# giraffe_bosch.net
KiCad netlist of a schematic drawn in EAGLE
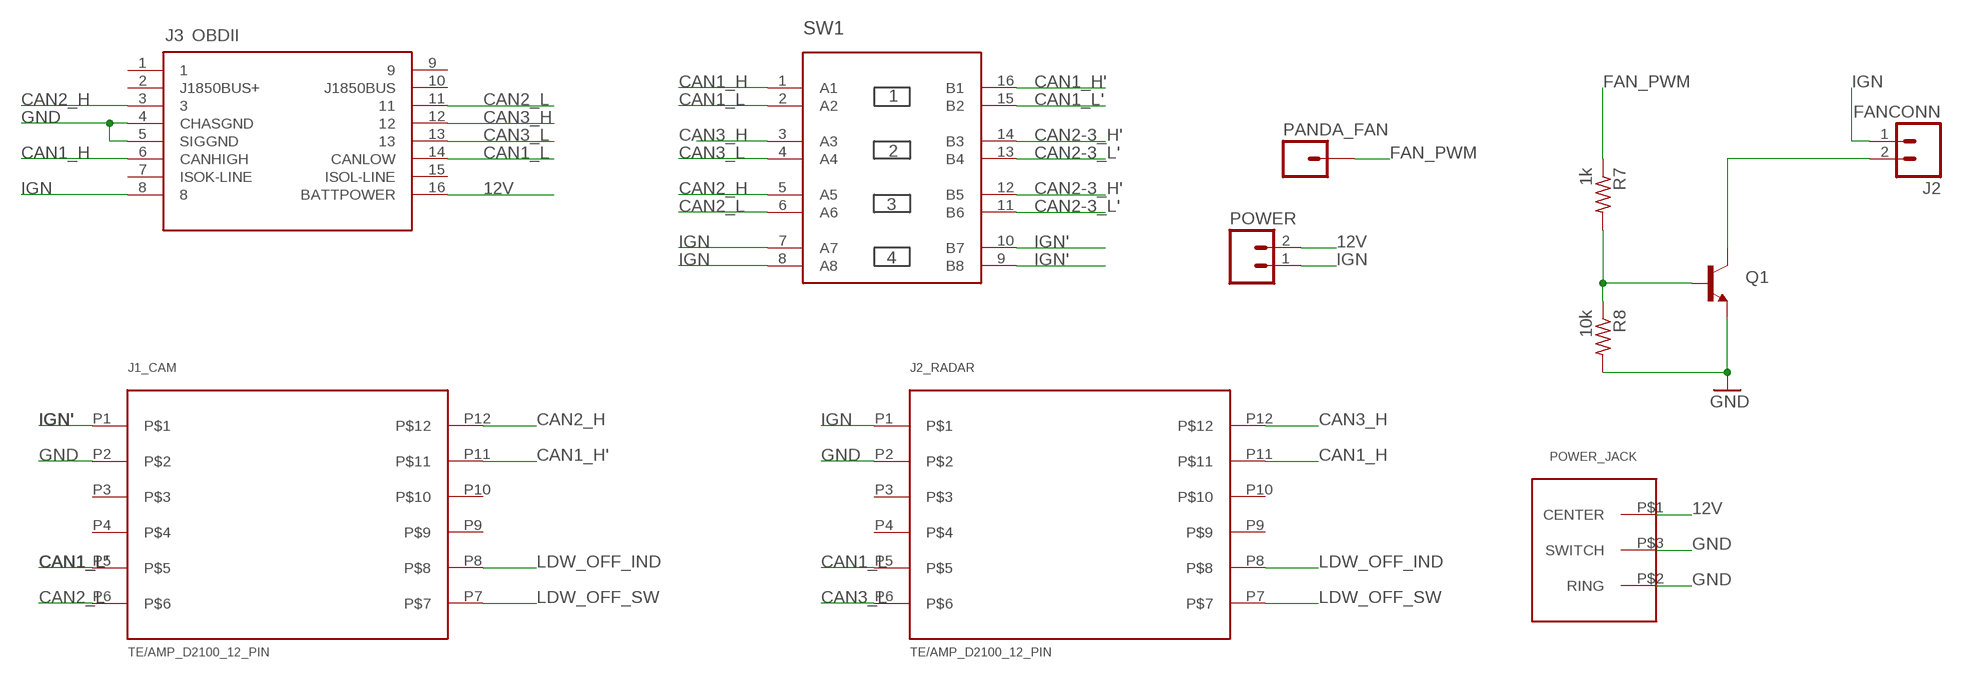
[diagram p0: schematic, sheet 1]

(export (version "E")
  (design (tool "Eeschema 10.0.6"))
  (components
    (comp (ref "J1_CAM")
      (value "TE/AMP_D2100_12_PIN")
      (footprint "eagle-import:TE_AMP_D2100_12_PIN")
      (libsource (lib "eagle-import") (part "TE/AMP_D2100_12_PIN"))
    )
    (comp (ref "J2")
      (value "FANCONN")
      (footprint "eagle-import:1.25CONN")
      (libsource (lib "eagle-import") (part "FANCONN"))
    )
    (comp (ref "J2_RADAR")
      (value "TE/AMP_D2100_12_PIN")
      (footprint "eagle-import:TE_AMP_D2100_12_PIN")
      (libsource (lib "eagle-import") (part "TE/AMP_D2100_12_PIN"))
    )
    (comp (ref "J3")
      (value "OBDIIFEMALE")
      (footprint "eagle-import:OBDII-FEMALE")
      (libsource (lib "eagle-import") (part "OBDIIFEMALE"))
    )
    (comp (ref "PANDA_FAN")
      (value "M01PTH")
      (footprint "eagle-import:1X01")
      (libsource (lib "eagle-import") (part "M01PTH"))
    )
    (comp (ref "POWER")
      (value "M02PTH")
      (footprint "eagle-import:1X02")
      (libsource (lib "eagle-import") (part "M02PTH"))
    )
    (comp (ref "POWER_JACK")
      (value "PJ-006A-SMT")
      (footprint "eagle-import:PJ-006A-SMT")
      (libsource (lib "eagle-import") (part "PJ-006A-SMT"))
    )
    (comp (ref "Q1")
      (value "MMBT2222A")
      (footprint "eagle-import:SOT23-3")
      (libsource (lib "eagle-import") (part "TRANSISTOR_NPNMMBT2222A"))
    )
    (comp (ref "R7")
      (value "1k")
      (footprint "eagle-import:R0603")
      (libsource (lib "eagle-import") (part "R-US_R0603"))
    )
    (comp (ref "R8")
      (value "10k")
      (footprint "eagle-import:R0603")
      (libsource (lib "eagle-import") (part "R-US_R0603"))
    )
    (comp (ref "SW1")
      (value "4XDPSTSMT")
      (footprint "eagle-import:4-DPST")
      (libsource (lib "eagle-import") (part "4XDPSTSMT"))
    )
  )
  (nets
    (net (code "1") (name "/12V") (class "Default")
      (node (ref "J3") (pin "16") (pinfunction "BATTPOWER_16") (pintype "bidirectional"))
      (node (ref "POWER") (pin "2") (pinfunction "2_2") (pintype "passive"))
      (node (ref "POWER_JACK") (pin "P$1") (pinfunction "CENTER_P$1") (pintype "power_in"))
    )
    (net (code "2") (name "/CAN1_H") (class "Default")
      (node (ref "J2_RADAR") (pin "P11") (pinfunction "P$11_P11") (pintype "bidirectional"))
      (node (ref "J3") (pin "6") (pinfunction "CANHIGH_6") (pintype "bidirectional"))
      (node (ref "SW1") (pin "1") (pinfunction "A1_1") (pintype "bidirectional"))
    )
    (net (code "3") (name "/CAN1_H'") (class "Default")
      (node (ref "J1_CAM") (pin "P11") (pinfunction "P$11_P11") (pintype "bidirectional"))
      (node (ref "SW1") (pin "16") (pinfunction "B1_16") (pintype "bidirectional"))
    )
    (net (code "4") (name "/CAN1_L") (class "Default")
      (node (ref "J2_RADAR") (pin "P5") (pinfunction "P$5_P5") (pintype "bidirectional"))
      (node (ref "J3") (pin "14") (pinfunction "CANLOW_14") (pintype "bidirectional"))
      (node (ref "SW1") (pin "2") (pinfunction "A2_2") (pintype "bidirectional"))
    )
    (net (code "5") (name "/CAN1_L'") (class "Default")
      (node (ref "J1_CAM") (pin "P5") (pinfunction "P$5_P5") (pintype "bidirectional"))
      (node (ref "SW1") (pin "15") (pinfunction "B2_15") (pintype "bidirectional"))
    )
    (net (code "6") (name "/CAN2-3_H'") (class "Default")
      (node (ref "SW1") (pin "12") (pinfunction "B5_12") (pintype "bidirectional"))
      (node (ref "SW1") (pin "14") (pinfunction "B3_14") (pintype "bidirectional"))
    )
    (net (code "7") (name "/CAN2-3_L'") (class "Default")
      (node (ref "SW1") (pin "11") (pinfunction "B6_11") (pintype "bidirectional"))
      (node (ref "SW1") (pin "13") (pinfunction "B4_13") (pintype "bidirectional"))
    )
    (net (code "8") (name "/CAN2_H") (class "Default")
      (node (ref "J1_CAM") (pin "P12") (pinfunction "P$12_P12") (pintype "bidirectional"))
      (node (ref "J3") (pin "3") (pinfunction "3_3") (pintype "bidirectional"))
      (node (ref "SW1") (pin "5") (pinfunction "A5_5") (pintype "bidirectional"))
    )
    (net (code "9") (name "/CAN2_L") (class "Default")
      (node (ref "J1_CAM") (pin "P6") (pinfunction "P$6_P6") (pintype "bidirectional"))
      (node (ref "J3") (pin "11") (pinfunction "11_11") (pintype "bidirectional"))
      (node (ref "SW1") (pin "6") (pinfunction "A6_6") (pintype "bidirectional"))
    )
    (net (code "10") (name "/CAN3_H") (class "Default")
      (node (ref "J2_RADAR") (pin "P12") (pinfunction "P$12_P12") (pintype "bidirectional"))
      (node (ref "J3") (pin "12") (pinfunction "12_12") (pintype "bidirectional"))
      (node (ref "SW1") (pin "3") (pinfunction "A3_3") (pintype "bidirectional"))
    )
    (net (code "11") (name "/CAN3_L") (class "Default")
      (node (ref "J2_RADAR") (pin "P6") (pinfunction "P$6_P6") (pintype "bidirectional"))
      (node (ref "J3") (pin "13") (pinfunction "13_13") (pintype "bidirectional"))
      (node (ref "SW1") (pin "4") (pinfunction "A4_4") (pintype "bidirectional"))
    )
    (net (code "12") (name "/FAN_PWM") (class "Default")
      (node (ref "PANDA_FAN") (pin "1") (pinfunction "1_1") (pintype "passive"))
      (node (ref "R7") (pin "1") (pinfunction "1_1") (pintype "passive"))
    )
    (net (code "13") (name "/IGN") (class "Default")
      (node (ref "J2") (pin "1") (pinfunction "1_1") (pintype "passive"))
      (node (ref "J2_RADAR") (pin "P1") (pinfunction "P$1_P1") (pintype "bidirectional"))
      (node (ref "J3") (pin "8") (pinfunction "8_8") (pintype "bidirectional"))
      (node (ref "POWER") (pin "1") (pinfunction "1_1") (pintype "passive"))
      (node (ref "SW1") (pin "7") (pinfunction "A7_7") (pintype "bidirectional"))
      (node (ref "SW1") (pin "8") (pinfunction "A8_8") (pintype "bidirectional"))
    )
    (net (code "14") (name "/IGN'") (class "Default")
      (node (ref "J1_CAM") (pin "P1") (pinfunction "P$1_P1") (pintype "bidirectional"))
      (node (ref "SW1") (pin "10") (pinfunction "B7_10") (pintype "bidirectional"))
      (node (ref "SW1") (pin "9") (pinfunction "B8_9") (pintype "bidirectional"))
    )
    (net (code "15") (name "/LDW_OFF_IND") (class "Default")
      (node (ref "J1_CAM") (pin "P8") (pinfunction "P$8_P8") (pintype "bidirectional"))
      (node (ref "J2_RADAR") (pin "P8") (pinfunction "P$8_P8") (pintype "bidirectional"))
    )
    (net (code "16") (name "/LDW_OFF_SW") (class "Default")
      (node (ref "J1_CAM") (pin "P7") (pinfunction "P$7_P7") (pintype "bidirectional"))
      (node (ref "J2_RADAR") (pin "P7") (pinfunction "P$7_P7") (pintype "bidirectional"))
    )
    (net (code "17") (name "GND") (class "Default")
      (node (ref "J1_CAM") (pin "P2") (pinfunction "P$2_P2") (pintype "bidirectional"))
      (node (ref "J2_RADAR") (pin "P2") (pinfunction "P$2_P2") (pintype "bidirectional"))
      (node (ref "J3") (pin "4") (pinfunction "CHASGND_4") (pintype "bidirectional"))
      (node (ref "J3") (pin "5") (pinfunction "SIGGND_5") (pintype "bidirectional"))
      (node (ref "POWER_JACK") (pin "P$2") (pinfunction "RING_P$2") (pintype "power_in"))
      (node (ref "POWER_JACK") (pin "P$3") (pinfunction "SWITCH_P$3") (pintype "power_in"))
      (node (ref "Q1") (pin "2") (pinfunction "E_2") (pintype "passive"))
      (node (ref "R8") (pin "2") (pinfunction "2_2") (pintype "passive"))
    )
    (net (code "18") (name "Net-(Q1-B)") (class "Default")
      (node (ref "Q1") (pin "1") (pinfunction "B_1") (pintype "passive"))
      (node (ref "R7") (pin "2") (pinfunction "2_2") (pintype "passive"))
      (node (ref "R8") (pin "1") (pinfunction "1_1") (pintype "passive"))
    )
    (net (code "19") (name "Net-(Q1-C)") (class "Default")
      (node (ref "J2") (pin "2") (pinfunction "2_2") (pintype "passive"))
      (node (ref "Q1") (pin "3") (pinfunction "C_3") (pintype "passive"))
    )
    (net (code "20") (name "unconnected-(J1_CAM-P$3-PadP3)") (class "Default")
      (node (ref "J1_CAM") (pin "P3") (pinfunction "P$3_P3") (pintype "bidirectional"))
    )
    (net (code "21") (name "unconnected-(J1_CAM-P$4-PadP4)") (class "Default")
      (node (ref "J1_CAM") (pin "P4") (pinfunction "P$4_P4") (pintype "bidirectional"))
    )
    (net (code "22") (name "unconnected-(J1_CAM-P$9-PadP9)") (class "Default")
      (node (ref "J1_CAM") (pin "P9") (pinfunction "P$9_P9") (pintype "bidirectional"))
    )
    (net (code "23") (name "unconnected-(J1_CAM-P$10-PadP10)") (class "Default")
      (node (ref "J1_CAM") (pin "P10") (pinfunction "P$10_P10") (pintype "bidirectional"))
    )
    (net (code "24") (name "unconnected-(J2_RADAR-P$3-PadP3)") (class "Default")
      (node (ref "J2_RADAR") (pin "P3") (pinfunction "P$3_P3") (pintype "bidirectional"))
    )
    (net (code "25") (name "unconnected-(J2_RADAR-P$4-PadP4)") (class "Default")
      (node (ref "J2_RADAR") (pin "P4") (pinfunction "P$4_P4") (pintype "bidirectional"))
    )
    (net (code "26") (name "unconnected-(J2_RADAR-P$9-PadP9)") (class "Default")
      (node (ref "J2_RADAR") (pin "P9") (pinfunction "P$9_P9") (pintype "bidirectional"))
    )
    (net (code "27") (name "unconnected-(J2_RADAR-P$10-PadP10)") (class "Default")
      (node (ref "J2_RADAR") (pin "P10") (pinfunction "P$10_P10") (pintype "bidirectional"))
    )
    (net (code "28") (name "unconnected-(J3-ISOK-LINE-Pad7)") (class "Default")
      (node (ref "J3") (pin "7") (pinfunction "ISOK-LINE_7") (pintype "bidirectional"))
    )
    (net (code "29") (name "unconnected-(J3-ISOL-LINE-Pad15)") (class "Default")
      (node (ref "J3") (pin "15") (pinfunction "ISOL-LINE_15") (pintype "bidirectional"))
    )
    (net (code "30") (name "unconnected-(J3-J1850BUS+-Pad2)") (class "Default")
      (node (ref "J3") (pin "2") (pinfunction "J1850BUS+_2") (pintype "bidirectional"))
    )
    (net (code "31") (name "unconnected-(J3-J1850BUS-Pad10)") (class "Default")
      (node (ref "J3") (pin "10") (pinfunction "J1850BUS_10") (pintype "bidirectional"))
    )
    (net (code "32") (name "unconnected-(J3-Pad1)") (class "Default")
      (node (ref "J3") (pin "1") (pinfunction "1_1") (pintype "bidirectional"))
    )
    (net (code "33") (name "unconnected-(J3-Pad9)") (class "Default")
      (node (ref "J3") (pin "9") (pinfunction "9_9") (pintype "bidirectional"))
    )
  )
)
